# infra_stlink.net
KiCad netlist of a schematic drawn in Altium Designer
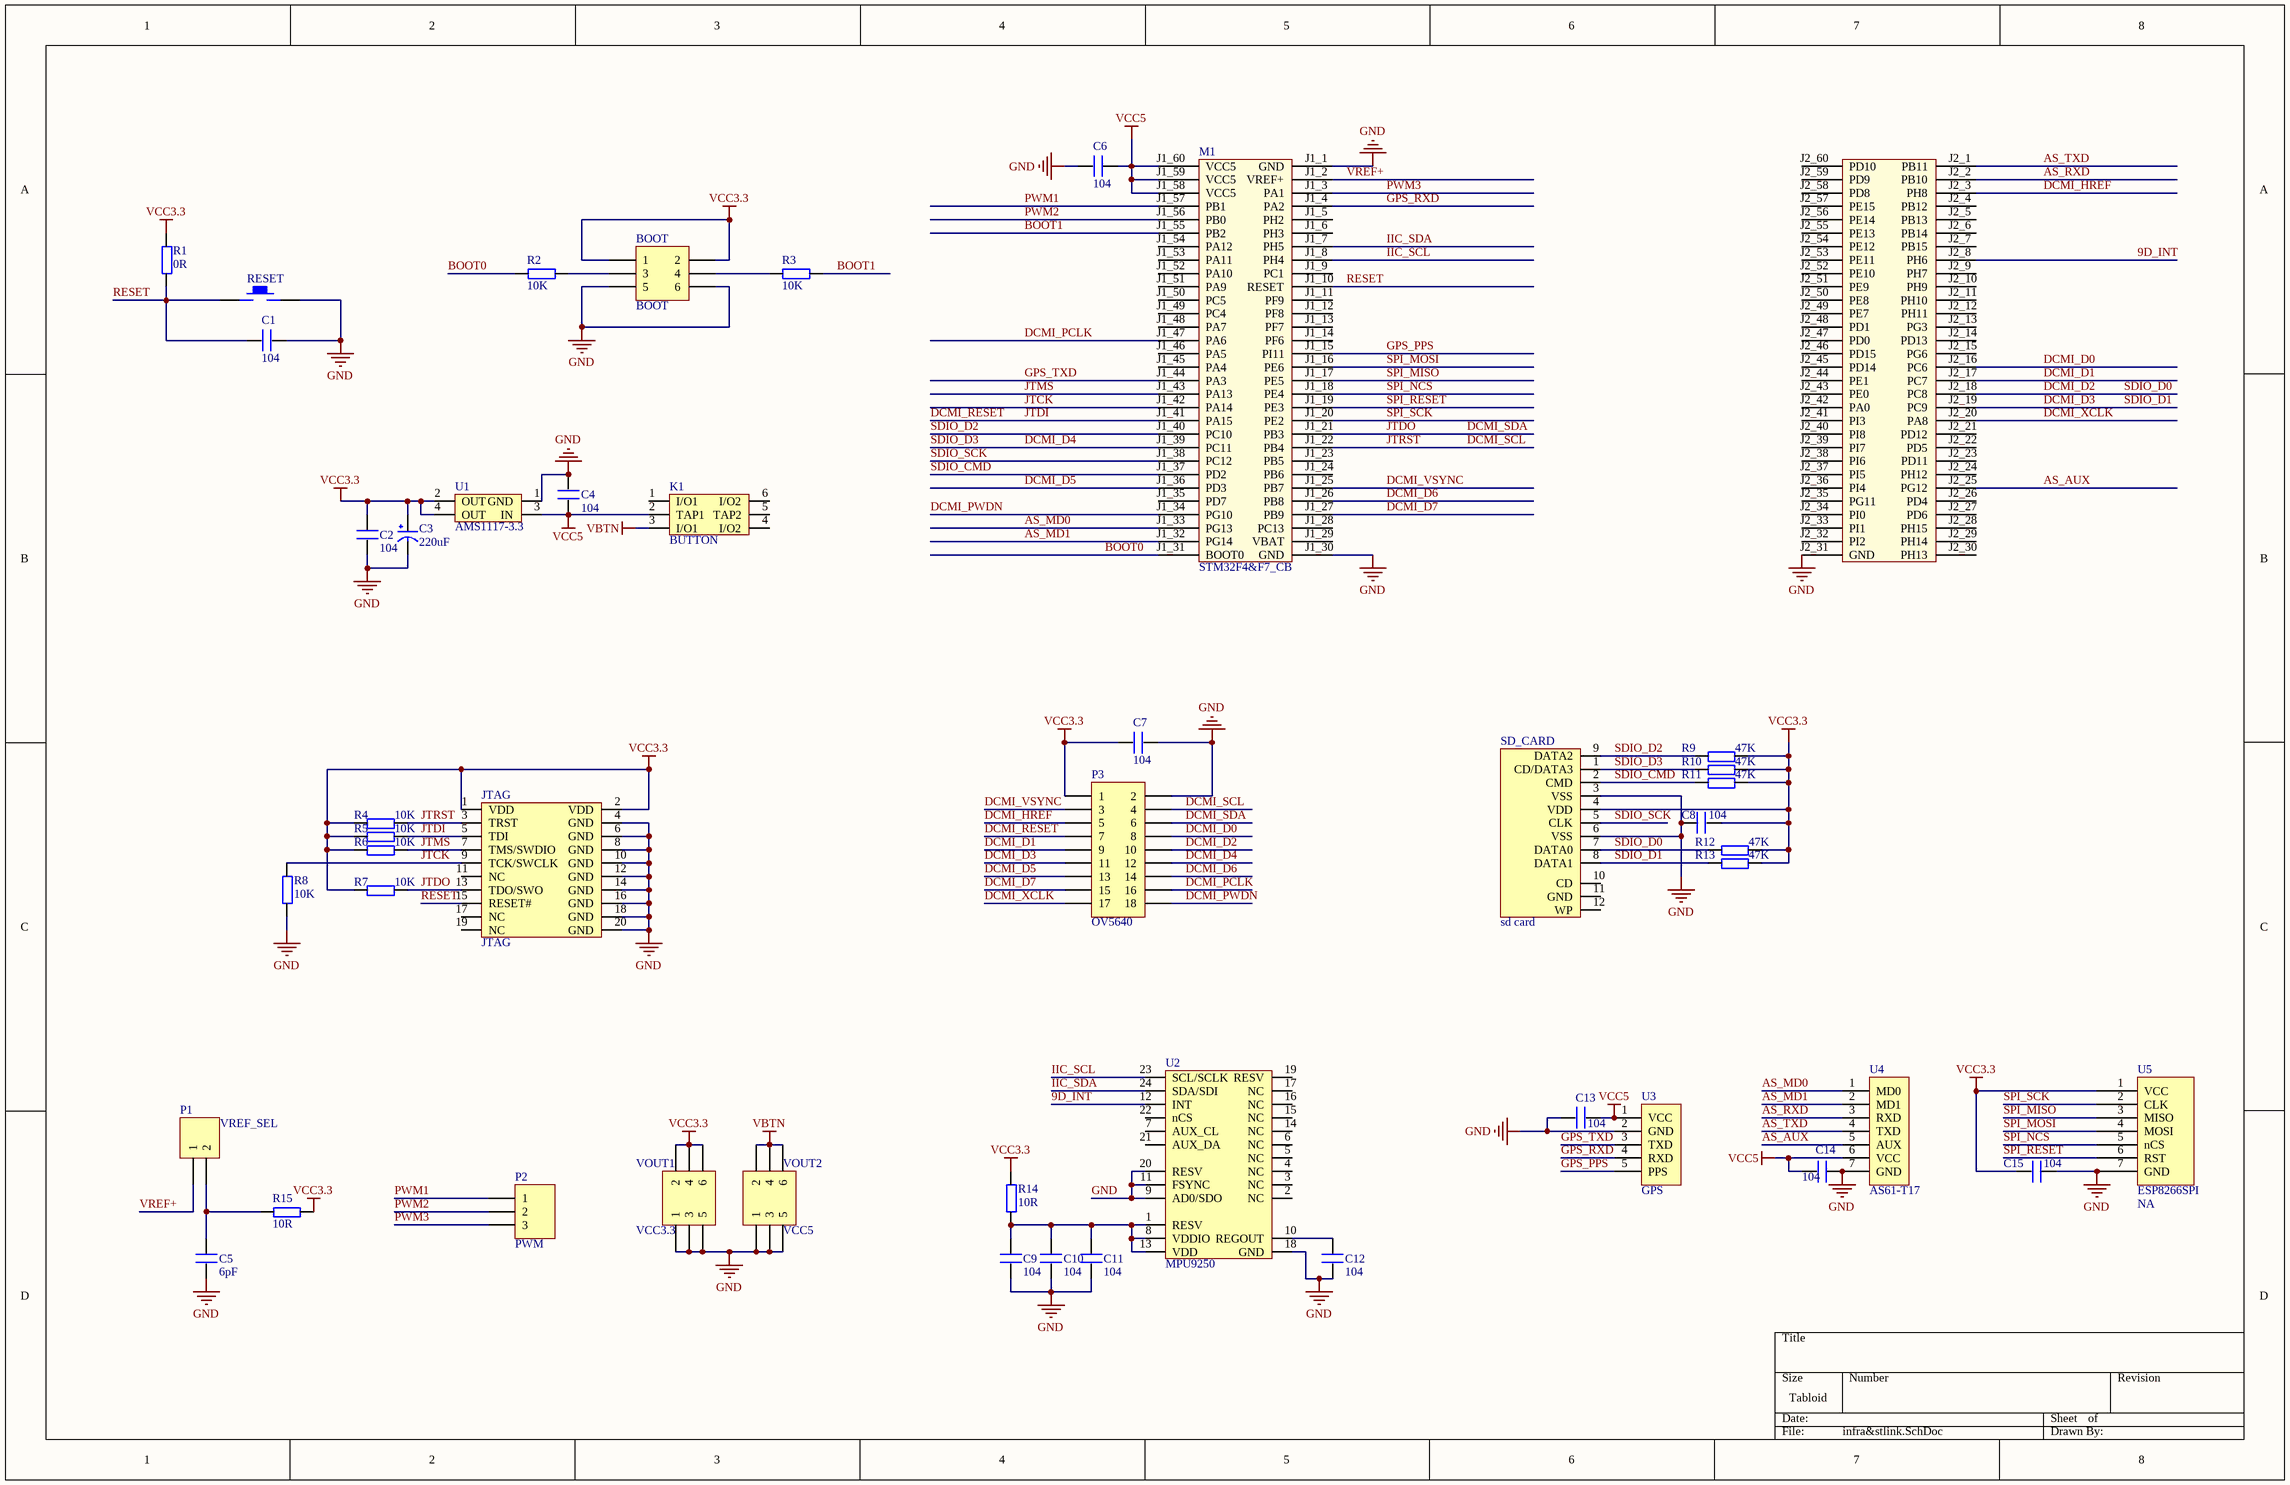
[diagram p0: infra&stlink.SchDoc]

(export (version "E")
  (design (tool "Eeschema 10.0.6"))
  (components
    (comp (ref "BOOT")
      (value "BOOT")
      (footprint "HDR2X3")
      (description "Header, 3-Pin, Dual row")
      (fields (field (name "PUBLISHER") "Altium Limited"))
      (libsource (lib "阿波罗STM32F4&F7底板封装库") (part "Header 3X2"))
    )
    (comp (ref "C1") (value "104") (footprint "0805") (libsource (lib "阿波罗STM32F4&F7底板封装库") (part "C")))
    (comp (ref "C2") (value "104") (footprint "0805") (libsource (lib "阿波罗STM32F4&F7底板封装库") (part "C")))
    (comp (ref "C3")
      (value "220uF")
      (footprint "CC6.56.5")
      (libsource (lib "阿波罗STM32F4&F7底板封装库") (part "CAP"))
    )
    (comp (ref "C4") (value "104") (footprint "0805") (libsource (lib "阿波罗STM32F4&F7底板封装库") (part "C")))
    (comp (ref "C5") (value "6pF") (footprint "0805") (libsource (lib "STM32F767核心板封装库") (part "C")))
    (comp (ref "C6") (value "104") (footprint "0805") (libsource (lib "阿波罗STM32F4&F7底板封装库") (part "C")))
    (comp (ref "C7") (value "104") (footprint "0805") (libsource (lib "STM32F767核心板封装库") (part "C")))
    (comp (ref "C8") (value "104") (footprint "0805") (libsource (lib "阿波罗STM32F4&F7底板封装库") (part "C")))
    (comp (ref "C9") (value "104") (footprint "0805") (libsource (lib "阿波罗STM32F4&F7底板封装库") (part "C")))
    (comp (ref "C10") (value "104") (footprint "0805") (libsource (lib "阿波罗STM32F4&F7底板封装库") (part "C")))
    (comp (ref "C11") (value "104") (footprint "0805") (libsource (lib "阿波罗STM32F4&F7底板封装库") (part "C")))
    (comp (ref "C12") (value "104") (footprint "0805") (libsource (lib "阿波罗STM32F4&F7底板封装库") (part "C")))
    (comp (ref "C13") (value "104") (footprint "0805") (libsource (lib "阿波罗STM32F4&F7底板封装库") (part "C")))
    (comp (ref "C14") (value "104") (footprint "0805") (libsource (lib "阿波罗STM32F4&F7底板封装库") (part "C")))
    (comp (ref "C15") (value "104") (footprint "0805") (libsource (lib "阿波罗STM32F4&F7底板封装库") (part "C")))
    (comp (ref "JTAG")
      (value "JTAG")
      (footprint "JTAG_20")
      (libsource (lib "阿波罗STM32F4&F7底板封装库") (part "JTAG"))
    )
    (comp (ref "K1")
      (value "BUTTON")
      (footprint "BTN8.5*8.5")
      (libsource (lib "阿波罗STM32F4&F7底板封装库") (part "BUTTON"))
    )
    (comp (ref "M1")
      (value "STM32F4&F7_CB")
      (footprint "STM32F4&F7_CB")
      (description "F429/746 Core Board")
      (libsource (lib "阿波罗STM32F4&F7底板封装库") (part "STM32F4&F7_CB"))
    )
    (comp (ref "P1")
      (value "VREF_SEL")
      (footprint "HDR1X2")
      (description "Header, 2-Pin")
      (fields (field (name "PUBLISHER") "Altium Limited"))
      (libsource (lib "阿波罗STM32F4&F7底板封装库") (part "Header 2"))
    )
    (comp (ref "P2")
      (value "PWM")
      (footprint "HDR1X3")
      (description "Header, 3-Pin")
      (fields (field (name "PUBLISHER") "Altium Limited"))
      (libsource (lib "Miscellaneous Connectors") (part "Header 3"))
    )
    (comp (ref "P3")
      (value "OV5640")
      (footprint "HDR2X9")
      (description "Header, 9-Pin, Dual row")
      (fields (field (name "PUBLISHER") "Altium Limited"))
      (libsource (lib "阿波罗STM32F4&F7底板封装库") (part "Header 9X2"))
    )
    (comp (ref "R1") (value "0R") (footprint "0805") (libsource (lib "STM32F767核心板封装库") (part "R")))
    (comp (ref "R2") (value "10K") (footprint "0805") (libsource (lib "STM32F767核心板封装库") (part "R")))
    (comp (ref "R3") (value "10K") (footprint "0805") (libsource (lib "STM32F767核心板封装库") (part "R")))
    (comp (ref "R4") (value "10K") (footprint "0805") (libsource (lib "STM32F767核心板封装库") (part "R")))
    (comp (ref "R5") (value "10K") (footprint "0805") (libsource (lib "STM32F767核心板封装库") (part "R")))
    (comp (ref "R6") (value "10K") (footprint "0805") (libsource (lib "STM32F767核心板封装库") (part "R")))
    (comp (ref "R7") (value "10K") (footprint "0805") (libsource (lib "STM32F767核心板封装库") (part "R")))
    (comp (ref "R8") (value "10K") (footprint "0805") (libsource (lib "STM32F767核心板封装库") (part "R")))
    (comp (ref "R9") (value "47K") (footprint "0805") (libsource (lib "STM32F767核心板封装库") (part "R")))
    (comp (ref "R10") (value "47K") (footprint "0805") (libsource (lib "STM32F767核心板封装库") (part "R")))
    (comp (ref "R11") (value "47K") (footprint "0805") (libsource (lib "STM32F767核心板封装库") (part "R")))
    (comp (ref "R12") (value "47K") (footprint "0805") (libsource (lib "STM32F767核心板封装库") (part "R")))
    (comp (ref "R13") (value "47K") (footprint "0805") (libsource (lib "STM32F767核心板封装库") (part "R")))
    (comp (ref "R14") (value "10R") (footprint "0805") (libsource (lib "STM32F767核心板封装库") (part "R")))
    (comp (ref "R15") (value "10R") (footprint "0805") (libsource (lib "STM32F767核心板封装库") (part "R")))
    (comp (ref "RESET")
      (value "KEY_M")
      (footprint "KEY_M")
      (libsource (lib "阿波罗STM32F4&F7底板封装库") (part "KEY_M"))
    )
    (comp (ref "SD_CARD")
      (value "sd card")
      (footprint "SDCARD_L")
      (libsource (lib "阿波罗STM32F4&F7底板封装库") (part "sd card"))
    )
    (comp (ref "U1")
      (value "AMS1117-3.3")
      (footprint "AMS1117")
      (libsource (lib "阿波罗STM32F4&F7底板封装库") (part "AMS1117"))
    )
    (comp (ref "U2")
      (value "MPU9250")
      (footprint "QFN24-t")
      (description "9轴运动处理传感器")
      (libsource (lib "阿波罗STM32F4&F7底板封装库") (part "MPU9250"))
    )
    (comp (ref "U3")
      (value "GPS")
      (footprint "HDR1X5")
      (description "Header, 5-Pin")
      (fields (field (name "PUBLISHER") "Altium Limited"))
      (libsource (lib "Miscellaneous Connectors") (part "Header 5"))
    )
    (comp (ref "U4")
      (value "AS61-T17")
      (footprint "HDR1X7")
      (description "Header, 7-Pin")
      (fields (field (name "PUBLISHER") "Altium Limited"))
      (libsource (lib "Miscellaneous Connectors") (part "Header 7"))
    )
    (comp (ref "U5")
      (value "NA")
      (footprint "Edge Connector7")
      (libsource (lib "esp8266spi") (part "ESP8266SPI"))
    )
    (comp (ref "VOUT1")
      (value "VCC3.3")
      (footprint "HDR2X3")
      (description "Header, 3-Pin, Dual row")
      (fields (field (name "PUBLISHER") "Altium Limited"))
      (libsource (lib "Miscellaneous Connectors") (part "Header 3X2"))
    )
    (comp (ref "VOUT2")
      (value "VCC5")
      (footprint "HDR2X3")
      (description "Header, 3-Pin, Dual row")
      (fields (field (name "PUBLISHER") "Altium Limited"))
      (libsource (lib "Miscellaneous Connectors") (part "Header 3X2"))
    )
  )
  (nets
    (net (code "1") (name "/9D_INT") (class "Default")
      (node (ref "M1") (pin "J2_8") (pinfunction "PH6_J2_8") (pintype "passive"))
      (node (ref "U2") (pin "12") (pinfunction "INT_12") (pintype "passive"))
    )
    (net (code "2") (name "/AS_AUX") (class "Default")
      (node (ref "M1") (pin "J2_25") (pinfunction "PG12_J2_25") (pintype "passive"))
      (node (ref "U4") (pin "5") (pinfunction "AUX_5") (pintype "passive"))
    )
    (net (code "3") (name "/AS_MD0") (class "Default")
      (node (ref "M1") (pin "J1_33") (pinfunction "PG13_J1_33") (pintype "passive"))
      (node (ref "U4") (pin "1") (pinfunction "MD0_1") (pintype "passive"))
    )
    (net (code "4") (name "/AS_MD1") (class "Default")
      (node (ref "M1") (pin "J1_32") (pinfunction "PG14_J1_32") (pintype "passive"))
      (node (ref "U4") (pin "2") (pinfunction "MD1_2") (pintype "passive"))
    )
    (net (code "5") (name "/AS_RXD") (class "Default")
      (node (ref "M1") (pin "J2_2") (pinfunction "PB10_J2_2") (pintype "passive"))
      (node (ref "U4") (pin "3") (pinfunction "RXD_3") (pintype "passive"))
    )
    (net (code "6") (name "/AS_TXD") (class "Default")
      (node (ref "M1") (pin "J2_1") (pinfunction "PB11_J2_1") (pintype "passive"))
      (node (ref "U4") (pin "4") (pinfunction "TXD_4") (pintype "passive"))
    )
    (net (code "7") (name "/BOOT0") (class "Default")
      (node (ref "M1") (pin "J1_31") (pinfunction "BOOT0_J1_31") (pintype "passive"))
      (node (ref "R2") (pin "1") (pintype "passive"))
    )
    (net (code "8") (name "/BOOT1") (class "Default")
      (node (ref "M1") (pin "J1_55") (pinfunction "PB2_J1_55") (pintype "passive"))
      (node (ref "R3") (pin "2") (pintype "passive"))
    )
    (net (code "9") (name "/DCMI_D0") (class "Default")
      (node (ref "M1") (pin "J2_16") (pinfunction "PC6_J2_16") (pintype "passive"))
      (node (ref "P3") (pin "8") (pinfunction "8_8") (pintype "passive"))
    )
    (net (code "10") (name "/DCMI_D1") (class "Default")
      (node (ref "M1") (pin "J2_17") (pinfunction "PC7_J2_17") (pintype "passive"))
      (node (ref "P3") (pin "9") (pinfunction "9_9") (pintype "passive"))
    )
    (net (code "11") (name "/DCMI_D2") (class "Default")
      (node (ref "M1") (pin "J2_18") (pinfunction "PC8_J2_18") (pintype "passive"))
      (node (ref "P3") (pin "10") (pinfunction "10_10") (pintype "passive"))
      (node (ref "R12") (pin "1") (pintype "passive"))
      (node (ref "SD_CARD") (pin "7") (pinfunction "DATA0_7") (pintype "passive"))
    )
    (net (code "12") (name "/DCMI_D3") (class "Default")
      (node (ref "M1") (pin "J2_19") (pinfunction "PC9_J2_19") (pintype "passive"))
      (node (ref "P3") (pin "11") (pinfunction "11_11") (pintype "passive"))
      (node (ref "R13") (pin "1") (pintype "passive"))
      (node (ref "SD_CARD") (pin "8") (pinfunction "DATA1_8") (pintype "passive"))
    )
    (net (code "13") (name "/DCMI_D4") (class "Default")
      (node (ref "M1") (pin "J1_39") (pinfunction "PC11_J1_39") (pintype "passive"))
      (node (ref "P3") (pin "12") (pinfunction "12_12") (pintype "passive"))
      (node (ref "R10") (pin "1") (pintype "passive"))
      (node (ref "SD_CARD") (pin "1") (pinfunction "CD/DATA3_1") (pintype "passive"))
    )
    (net (code "14") (name "/DCMI_D5") (class "Default")
      (node (ref "M1") (pin "J1_36") (pinfunction "PD3_J1_36") (pintype "passive"))
      (node (ref "P3") (pin "13") (pinfunction "13_13") (pintype "passive"))
    )
    (net (code "15") (name "/DCMI_D6") (class "Default")
      (node (ref "M1") (pin "J1_26") (pinfunction "PB8_J1_26") (pintype "passive"))
      (node (ref "P3") (pin "14") (pinfunction "14_14") (pintype "passive"))
    )
    (net (code "16") (name "/DCMI_D7") (class "Default")
      (node (ref "M1") (pin "J1_27") (pinfunction "PB9_J1_27") (pintype "passive"))
      (node (ref "P3") (pin "15") (pinfunction "15_15") (pintype "passive"))
    )
    (net (code "17") (name "/DCMI_HREF") (class "Default")
      (node (ref "M1") (pin "J2_3") (pinfunction "PH8_J2_3") (pintype "passive"))
      (node (ref "P3") (pin "5") (pinfunction "5_5") (pintype "passive"))
    )
    (net (code "18") (name "/DCMI_PCLK") (class "Default")
      (node (ref "M1") (pin "J1_47") (pinfunction "PA6_J1_47") (pintype "passive"))
      (node (ref "P3") (pin "16") (pinfunction "16_16") (pintype "passive"))
    )
    (net (code "19") (name "/DCMI_PWDN") (class "Default")
      (node (ref "M1") (pin "J1_34") (pinfunction "PG10_J1_34") (pintype "passive"))
      (node (ref "P3") (pin "18") (pinfunction "18_18") (pintype "passive"))
    )
    (net (code "20") (name "/DCMI_RESET") (class "Default")
      (node (ref "JTAG") (pin "5") (pinfunction "TDI_5") (pintype "passive"))
      (node (ref "M1") (pin "J1_41") (pinfunction "PA15_J1_41") (pintype "passive"))
      (node (ref "P3") (pin "7") (pinfunction "7_7") (pintype "passive"))
      (node (ref "R5") (pin "2") (pintype "passive"))
    )
    (net (code "21") (name "/DCMI_SCL") (class "Default")
      (node (ref "JTAG") (pin "3") (pinfunction "TRST_3") (pintype "passive"))
      (node (ref "M1") (pin "J1_22") (pinfunction "PB4_J1_22") (pintype "passive"))
      (node (ref "P3") (pin "4") (pinfunction "4_4") (pintype "passive"))
      (node (ref "R4") (pin "2") (pintype "passive"))
    )
    (net (code "22") (name "/DCMI_SDA") (class "Default")
      (node (ref "JTAG") (pin "13") (pinfunction "TDO/SWO_13") (pintype "passive"))
      (node (ref "M1") (pin "J1_21") (pinfunction "PB3_J1_21") (pintype "passive"))
      (node (ref "P3") (pin "6") (pinfunction "6_6") (pintype "passive"))
      (node (ref "R7") (pin "2") (pintype "passive"))
    )
    (net (code "23") (name "/DCMI_VSYNC") (class "Default")
      (node (ref "M1") (pin "J1_25") (pinfunction "PB7_J1_25") (pintype "passive"))
      (node (ref "P3") (pin "3") (pinfunction "3_3") (pintype "passive"))
    )
    (net (code "24") (name "/DCMI_XCLK") (class "Default")
      (node (ref "M1") (pin "J2_20") (pinfunction "PA8_J2_20") (pintype "passive"))
      (node (ref "P3") (pin "17") (pinfunction "17_17") (pintype "passive"))
    )
    (net (code "25") (name "/GPS_PPS") (class "Default")
      (node (ref "M1") (pin "J1_15") (pinfunction "PI11_J1_15") (pintype "passive"))
      (node (ref "U3") (pin "5") (pinfunction "PPS_5") (pintype "passive"))
    )
    (net (code "26") (name "/GPS_RXD") (class "Default")
      (node (ref "M1") (pin "J1_4") (pinfunction "PA2_J1_4") (pintype "passive"))
      (node (ref "U3") (pin "4") (pinfunction "RXD_4") (pintype "passive"))
    )
    (net (code "27") (name "/GPS_TXD") (class "Default")
      (node (ref "M1") (pin "J1_44") (pinfunction "PA3_J1_44") (pintype "passive"))
      (node (ref "U3") (pin "3") (pinfunction "TXD_3") (pintype "passive"))
    )
    (net (code "28") (name "/IIC_SCL") (class "Default")
      (node (ref "M1") (pin "J1_8") (pinfunction "PH4_J1_8") (pintype "passive"))
      (node (ref "U2") (pin "23") (pinfunction "SCL/SCLK_23") (pintype "passive"))
    )
    (net (code "29") (name "/IIC_SDA") (class "Default")
      (node (ref "M1") (pin "J1_7") (pinfunction "PH5_J1_7") (pintype "passive"))
      (node (ref "U2") (pin "24") (pinfunction "SDA/SDI_24") (pintype "passive"))
    )
    (net (code "30") (name "/JTCK") (class "Default")
      (node (ref "JTAG") (pin "9") (pinfunction "TCK/SWCLK_9") (pintype "passive"))
      (node (ref "M1") (pin "J1_42") (pinfunction "PA14_J1_42") (pintype "passive"))
      (node (ref "R8") (pin "2") (pintype "passive"))
    )
    (net (code "31") (name "/JTMS") (class "Default")
      (node (ref "JTAG") (pin "7") (pinfunction "TMS/SWDIO_7") (pintype "passive"))
      (node (ref "M1") (pin "J1_43") (pinfunction "PA13_J1_43") (pintype "passive"))
      (node (ref "R6") (pin "2") (pintype "passive"))
    )
    (net (code "32") (name "/PWM1") (class "Default")
      (node (ref "M1") (pin "J1_57") (pinfunction "PB1_J1_57") (pintype "passive"))
      (node (ref "P2") (pin "1") (pinfunction "1_1") (pintype "passive"))
    )
    (net (code "33") (name "/PWM2") (class "Default")
      (node (ref "M1") (pin "J1_56") (pinfunction "PB0_J1_56") (pintype "passive"))
      (node (ref "P2") (pin "2") (pinfunction "2_2") (pintype "passive"))
    )
    (net (code "34") (name "/PWM3") (class "Default")
      (node (ref "M1") (pin "J1_3") (pinfunction "PA1_J1_3") (pintype "passive"))
      (node (ref "P2") (pin "3") (pinfunction "3_3") (pintype "passive"))
    )
    (net (code "35") (name "/RESET") (class "Default")
      (node (ref "C1") (pin "1") (pintype "passive"))
      (node (ref "JTAG") (pin "15") (pinfunction "RESET#_15") (pintype "passive"))
      (node (ref "M1") (pin "J1_10") (pinfunction "RESET_J1_10") (pintype "passive"))
      (node (ref "R1") (pin "1") (pintype "passive"))
      (node (ref "RESET") (pin "1") (pinfunction "1_1") (pintype "passive"))
    )
    (net (code "36") (name "/SDIO_CMD") (class "Default")
      (node (ref "M1") (pin "J1_37") (pinfunction "PD2_J1_37") (pintype "passive"))
      (node (ref "R11") (pin "1") (pintype "passive"))
      (node (ref "SD_CARD") (pin "2") (pinfunction "CMD_2") (pintype "passive"))
    )
    (net (code "37") (name "/SDIO_D2") (class "Default")
      (node (ref "M1") (pin "J1_40") (pinfunction "PC10_J1_40") (pintype "passive"))
      (node (ref "R9") (pin "1") (pintype "passive"))
      (node (ref "SD_CARD") (pin "9") (pinfunction "DATA2_9") (pintype "passive"))
    )
    (net (code "38") (name "/SDIO_SCK") (class "Default")
      (node (ref "M1") (pin "J1_38") (pinfunction "PC12_J1_38") (pintype "passive"))
      (node (ref "SD_CARD") (pin "5") (pinfunction "CLK_5") (pintype "passive"))
    )
    (net (code "39") (name "/SPI_MISO") (class "Default")
      (node (ref "M1") (pin "J1_17") (pinfunction "PE5_J1_17") (pintype "passive"))
      (node (ref "U5") (pin "3") (pinfunction "MISO_3") (pintype "passive"))
    )
    (net (code "40") (name "/SPI_MOSI") (class "Default")
      (node (ref "M1") (pin "J1_16") (pinfunction "PE6_J1_16") (pintype "passive"))
      (node (ref "U5") (pin "4") (pinfunction "MOSI_4") (pintype "passive"))
    )
    (net (code "41") (name "/SPI_NCS") (class "Default")
      (node (ref "M1") (pin "J1_18") (pinfunction "PE4_J1_18") (pintype "passive"))
      (node (ref "U5") (pin "5") (pinfunction "nCS_5") (pintype "passive"))
    )
    (net (code "42") (name "/SPI_RESET") (class "Default")
      (node (ref "M1") (pin "J1_19") (pinfunction "PE3_J1_19") (pintype "passive"))
      (node (ref "U5") (pin "6") (pinfunction "RST_6") (pintype "passive"))
    )
    (net (code "43") (name "/SPI_SCK") (class "Default")
      (node (ref "M1") (pin "J1_20") (pinfunction "PE2_J1_20") (pintype "passive"))
      (node (ref "U5") (pin "2") (pinfunction "CLK_2") (pintype "passive"))
    )
    (net (code "44") (name "/VREF+") (class "Default")
      (node (ref "M1") (pin "J1_2") (pinfunction "VREF+_J1_2") (pintype "passive"))
      (node (ref "P1") (pin "1") (pinfunction "1_1") (pintype "passive"))
    )
    (net (code "45") (name "GND") (class "Default")
      (node (ref "BOOT") (pin "5") (pinfunction "5_5") (pintype "passive"))
      (node (ref "BOOT") (pin "6") (pinfunction "6_6") (pintype "passive"))
      (node (ref "C1") (pin "2") (pintype "passive"))
      (node (ref "C10") (pin "1") (pintype "passive"))
      (node (ref "C11") (pin "1") (pintype "passive"))
      (node (ref "C12") (pin "1") (pintype "passive"))
      (node (ref "C13") (pin "1") (pintype "passive"))
      (node (ref "C14") (pin "1") (pintype "passive"))
      (node (ref "C15") (pin "2") (pintype "passive"))
      (node (ref "C2") (pin "1") (pintype "passive"))
      (node (ref "C3") (pin "2") (pinfunction "GND_2") (pintype "passive"))
      (node (ref "C4") (pin "2") (pintype "passive"))
      (node (ref "C5") (pin "1") (pintype "passive"))
      (node (ref "C6") (pin "1") (pintype "passive"))
      (node (ref "C7") (pin "2") (pintype "passive"))
      (node (ref "C8") (pin "1") (pintype "passive"))
      (node (ref "C9") (pin "1") (pintype "passive"))
      (node (ref "JTAG") (pin "10") (pinfunction "GND_10") (pintype "passive"))
      (node (ref "JTAG") (pin "12") (pinfunction "GND_12") (pintype "passive"))
      (node (ref "JTAG") (pin "14") (pinfunction "GND_14") (pintype "passive"))
      (node (ref "JTAG") (pin "16") (pinfunction "GND_16") (pintype "passive"))
      (node (ref "JTAG") (pin "18") (pinfunction "GND_18") (pintype "passive"))
      (node (ref "JTAG") (pin "20") (pinfunction "GND_20") (pintype "passive"))
      (node (ref "JTAG") (pin "4") (pinfunction "GND_4") (pintype "passive"))
      (node (ref "JTAG") (pin "6") (pinfunction "GND_6") (pintype "passive"))
      (node (ref "JTAG") (pin "8") (pinfunction "GND_8") (pintype "passive"))
      (node (ref "M1") (pin "J1_1") (pinfunction "GND_J1_1") (pintype "passive"))
      (node (ref "M1") (pin "J1_30") (pinfunction "GND_J1_30") (pintype "passive"))
      (node (ref "M1") (pin "J2_31") (pinfunction "GND_J2_31") (pintype "passive"))
      (node (ref "P3") (pin "2") (pinfunction "2_2") (pintype "passive"))
      (node (ref "R8") (pin "1") (pintype "passive"))
      (node (ref "RESET") (pin "2") (pinfunction "2_2") (pintype "passive"))
      (node (ref "SD_CARD") (pin "3") (pinfunction "VSS_3") (pintype "passive"))
      (node (ref "SD_CARD") (pin "6") (pinfunction "VSS_6") (pintype "passive"))
      (node (ref "U1") (pin "1") (pinfunction "GND_1") (pintype "passive"))
      (node (ref "U2") (pin "11") (pinfunction "FSYNC_11") (pintype "passive"))
      (node (ref "U2") (pin "18") (pinfunction "GND_18") (pintype "passive"))
      (node (ref "U2") (pin "20") (pinfunction "RESV_20") (pintype "passive"))
      (node (ref "U2") (pin "9") (pinfunction "AD0/SDO_9") (pintype "passive"))
      (node (ref "U3") (pin "2") (pinfunction "GND_2") (pintype "passive"))
      (node (ref "U4") (pin "7") (pinfunction "GND_7") (pintype "passive"))
      (node (ref "U5") (pin "7") (pinfunction "GND_7") (pintype "passive"))
      (node (ref "VOUT1") (pin "1") (pinfunction "1_1") (pintype "passive"))
      (node (ref "VOUT1") (pin "3") (pinfunction "3_3") (pintype "passive"))
      (node (ref "VOUT1") (pin "5") (pinfunction "5_5") (pintype "passive"))
      (node (ref "VOUT2") (pin "1") (pinfunction "1_1") (pintype "passive"))
      (node (ref "VOUT2") (pin "3") (pinfunction "3_3") (pintype "passive"))
      (node (ref "VOUT2") (pin "5") (pinfunction "5_5") (pintype "passive"))
    )
    (net (code "46") (name "Net-(BOOT-Pad3)") (class "Default")
      (node (ref "BOOT") (pin "3") (pinfunction "3_3") (pintype "passive"))
      (node (ref "R2") (pin "2") (pintype "passive"))
    )
    (net (code "47") (name "Net-(BOOT-Pad4)") (class "Default")
      (node (ref "BOOT") (pin "4") (pinfunction "4_4") (pintype "passive"))
      (node (ref "R3") (pin "1") (pintype "passive"))
    )
    (net (code "48") (name "Net-(C5-Pad2)") (class "Default")
      (node (ref "C5") (pin "2") (pintype "passive"))
      (node (ref "P1") (pin "2") (pinfunction "2_2") (pintype "passive"))
      (node (ref "R15") (pin "1") (pintype "passive"))
    )
    (net (code "49") (name "Net-(U2-REGOUT)") (class "Default")
      (node (ref "C12") (pin "2") (pintype "passive"))
      (node (ref "U2") (pin "10") (pinfunction "REGOUT_10") (pintype "passive"))
    )
    (net (code "50") (name "Net-(U2-VDD)") (class "Default")
      (node (ref "C10") (pin "2") (pintype "passive"))
      (node (ref "C11") (pin "2") (pintype "passive"))
      (node (ref "C9") (pin "2") (pintype "passive"))
      (node (ref "R14") (pin "1") (pintype "passive"))
      (node (ref "U2") (pin "1") (pinfunction "RESV_1") (pintype "passive"))
      (node (ref "U2") (pin "13") (pinfunction "VDD_13") (pintype "passive"))
      (node (ref "U2") (pin "8") (pinfunction "VDDIO_8") (pintype "passive"))
    )
    (net (code "51") (name "VBTN") (class "Default")
      (node (ref "K1") (pin "3") (pinfunction "I/O1_3") (pintype "passive"))
      (node (ref "VOUT2") (pin "2") (pinfunction "2_2") (pintype "passive"))
      (node (ref "VOUT2") (pin "4") (pinfunction "4_4") (pintype "passive"))
      (node (ref "VOUT2") (pin "6") (pinfunction "6_6") (pintype "passive"))
    )
    (net (code "52") (name "VCC3.3") (class "Default")
      (node (ref "BOOT") (pin "1") (pinfunction "1_1") (pintype "passive"))
      (node (ref "BOOT") (pin "2") (pinfunction "2_2") (pintype "passive"))
      (node (ref "C15") (pin "1") (pintype "passive"))
      (node (ref "C2") (pin "2") (pintype "passive"))
      (node (ref "C3") (pin "1") (pinfunction "VCC_1") (pintype "passive"))
      (node (ref "C7") (pin "1") (pintype "passive"))
      (node (ref "C8") (pin "2") (pintype "passive"))
      (node (ref "JTAG") (pin "1") (pinfunction "VDD_1") (pintype "passive"))
      (node (ref "JTAG") (pin "2") (pinfunction "VDD_2") (pintype "passive"))
      (node (ref "P3") (pin "1") (pinfunction "1_1") (pintype "passive"))
      (node (ref "R1") (pin "2") (pintype "passive"))
      (node (ref "R10") (pin "2") (pintype "passive"))
      (node (ref "R11") (pin "2") (pintype "passive"))
      (node (ref "R12") (pin "2") (pintype "passive"))
      (node (ref "R13") (pin "2") (pintype "passive"))
      (node (ref "R14") (pin "2") (pintype "passive"))
      (node (ref "R15") (pin "2") (pintype "passive"))
      (node (ref "R4") (pin "1") (pintype "passive"))
      (node (ref "R5") (pin "1") (pintype "passive"))
      (node (ref "R6") (pin "1") (pintype "passive"))
      (node (ref "R7") (pin "1") (pintype "passive"))
      (node (ref "R9") (pin "2") (pintype "passive"))
      (node (ref "SD_CARD") (pin "4") (pinfunction "VDD_4") (pintype "passive"))
      (node (ref "U1") (pin "2") (pinfunction "OUT_2") (pintype "passive"))
      (node (ref "U1") (pin "4") (pinfunction "OUT_4") (pintype "passive"))
      (node (ref "U5") (pin "1") (pinfunction "VCC_1") (pintype "passive"))
      (node (ref "VOUT1") (pin "2") (pinfunction "2_2") (pintype "passive"))
      (node (ref "VOUT1") (pin "4") (pinfunction "4_4") (pintype "passive"))
      (node (ref "VOUT1") (pin "6") (pinfunction "6_6") (pintype "passive"))
    )
    (net (code "53") (name "VCC5") (class "Default")
      (node (ref "C13") (pin "2") (pintype "passive"))
      (node (ref "C14") (pin "2") (pintype "passive"))
      (node (ref "C4") (pin "1") (pintype "passive"))
      (node (ref "C6") (pin "2") (pintype "passive"))
      (node (ref "K1") (pin "2") (pinfunction "TAP1_2") (pintype "passive"))
      (node (ref "M1") (pin "J1_58") (pinfunction "VCC5_J1_58") (pintype "passive"))
      (node (ref "M1") (pin "J1_59") (pinfunction "VCC5_J1_59") (pintype "passive"))
      (node (ref "M1") (pin "J1_60") (pinfunction "VCC5_J1_60") (pintype "passive"))
      (node (ref "U1") (pin "3") (pinfunction "IN_3") (pintype "passive"))
      (node (ref "U3") (pin "1") (pinfunction "VCC_1") (pintype "passive"))
      (node (ref "U4") (pin "6") (pinfunction "VCC_6") (pintype "passive"))
    )
    (net (code "54") (name "unconnected-(JTAG-NC-Pad11)") (class "Default")
      (node (ref "JTAG") (pin "11") (pinfunction "NC_11") (pintype "passive"))
    )
    (net (code "55") (name "unconnected-(JTAG-NC-Pad17)") (class "Default")
      (node (ref "JTAG") (pin "17") (pinfunction "NC_17") (pintype "passive"))
    )
    (net (code "56") (name "unconnected-(JTAG-NC-Pad19)") (class "Default")
      (node (ref "JTAG") (pin "19") (pinfunction "NC_19") (pintype "passive"))
    )
    (net (code "57") (name "unconnected-(K1-I{slash}O1-Pad1)") (class "Default")
      (node (ref "K1") (pin "1") (pinfunction "I/O1_1") (pintype "passive"))
    )
    (net (code "58") (name "unconnected-(K1-I{slash}O2-Pad4)") (class "Default")
      (node (ref "K1") (pin "4") (pinfunction "I/O2_4") (pintype "passive"))
    )
    (net (code "59") (name "unconnected-(K1-I{slash}O2-Pad6)") (class "Default")
      (node (ref "K1") (pin "6") (pinfunction "I/O2_6") (pintype "passive"))
    )
    (net (code "60") (name "unconnected-(K1-TAP2-Pad5)") (class "Default")
      (node (ref "K1") (pin "5") (pinfunction "TAP2_5") (pintype "passive"))
    )
    (net (code "61") (name "unconnected-(M1-PA0-PadJ2_42)") (class "Default")
      (node (ref "M1") (pin "J2_42") (pinfunction "PA0_J2_42") (pintype "passive"))
    )
    (net (code "62") (name "unconnected-(M1-PA4-PadJ1_45)") (class "Default")
      (node (ref "M1") (pin "J1_45") (pinfunction "PA4_J1_45") (pintype "passive"))
    )
    (net (code "63") (name "unconnected-(M1-PA5-PadJ1_46)") (class "Default")
      (node (ref "M1") (pin "J1_46") (pinfunction "PA5_J1_46") (pintype "passive"))
    )
    (net (code "64") (name "unconnected-(M1-PA7-PadJ1_48)") (class "Default")
      (node (ref "M1") (pin "J1_48") (pinfunction "PA7_J1_48") (pintype "passive"))
    )
    (net (code "65") (name "unconnected-(M1-PA9-PadJ1_51)") (class "Default")
      (node (ref "M1") (pin "J1_51") (pinfunction "PA9_J1_51") (pintype "passive"))
    )
    (net (code "66") (name "unconnected-(M1-PA10-PadJ1_52)") (class "Default")
      (node (ref "M1") (pin "J1_52") (pinfunction "PA10_J1_52") (pintype "passive"))
    )
    (net (code "67") (name "unconnected-(M1-PA11-PadJ1_53)") (class "Default")
      (node (ref "M1") (pin "J1_53") (pinfunction "PA11_J1_53") (pintype "passive"))
    )
    (net (code "68") (name "unconnected-(M1-PA12-PadJ1_54)") (class "Default")
      (node (ref "M1") (pin "J1_54") (pinfunction "PA12_J1_54") (pintype "passive"))
    )
    (net (code "69") (name "unconnected-(M1-PB5-PadJ1_23)") (class "Default")
      (node (ref "M1") (pin "J1_23") (pinfunction "PB5_J1_23") (pintype "passive"))
    )
    (net (code "70") (name "unconnected-(M1-PB6-PadJ1_24)") (class "Default")
      (node (ref "M1") (pin "J1_24") (pinfunction "PB6_J1_24") (pintype "passive"))
    )
    (net (code "71") (name "unconnected-(M1-PB12-PadJ2_4)") (class "Default")
      (node (ref "M1") (pin "J2_4") (pinfunction "PB12_J2_4") (pintype "passive"))
    )
    (net (code "72") (name "unconnected-(M1-PB13-PadJ2_5)") (class "Default")
      (node (ref "M1") (pin "J2_5") (pinfunction "PB13_J2_5") (pintype "passive"))
    )
    (net (code "73") (name "unconnected-(M1-PB14-PadJ2_6)") (class "Default")
      (node (ref "M1") (pin "J2_6") (pinfunction "PB14_J2_6") (pintype "passive"))
    )
    (net (code "74") (name "unconnected-(M1-PB15-PadJ2_7)") (class "Default")
      (node (ref "M1") (pin "J2_7") (pinfunction "PB15_J2_7") (pintype "passive"))
    )
    (net (code "75") (name "unconnected-(M1-PC1-PadJ1_9)") (class "Default")
      (node (ref "M1") (pin "J1_9") (pinfunction "PC1_J1_9") (pintype "passive"))
    )
    (net (code "76") (name "unconnected-(M1-PC4-PadJ1_49)") (class "Default")
      (node (ref "M1") (pin "J1_49") (pinfunction "PC4_J1_49") (pintype "passive"))
    )
    (net (code "77") (name "unconnected-(M1-PC5-PadJ1_50)") (class "Default")
      (node (ref "M1") (pin "J1_50") (pinfunction "PC5_J1_50") (pintype "passive"))
    )
    (net (code "78") (name "unconnected-(M1-PC13-PadJ1_28)") (class "Default")
      (node (ref "M1") (pin "J1_28") (pinfunction "PC13_J1_28") (pintype "passive"))
    )
    (net (code "79") (name "unconnected-(M1-PD0-PadJ2_47)") (class "Default")
      (node (ref "M1") (pin "J2_47") (pinfunction "PD0_J2_47") (pintype "passive"))
    )
    (net (code "80") (name "unconnected-(M1-PD1-PadJ2_48)") (class "Default")
      (node (ref "M1") (pin "J2_48") (pinfunction "PD1_J2_48") (pintype "passive"))
    )
    (net (code "81") (name "unconnected-(M1-PD4-PadJ2_26)") (class "Default")
      (node (ref "M1") (pin "J2_26") (pinfunction "PD4_J2_26") (pintype "passive"))
    )
    (net (code "82") (name "unconnected-(M1-PD5-PadJ2_22)") (class "Default")
      (node (ref "M1") (pin "J2_22") (pinfunction "PD5_J2_22") (pintype "passive"))
    )
    (net (code "83") (name "unconnected-(M1-PD6-PadJ2_27)") (class "Default")
      (node (ref "M1") (pin "J2_27") (pinfunction "PD6_J2_27") (pintype "passive"))
    )
    (net (code "84") (name "unconnected-(M1-PD7-PadJ1_35)") (class "Default")
      (node (ref "M1") (pin "J1_35") (pinfunction "PD7_J1_35") (pintype "passive"))
    )
    (net (code "85") (name "unconnected-(M1-PD8-PadJ2_58)") (class "Default")
      (node (ref "M1") (pin "J2_58") (pinfunction "PD8_J2_58") (pintype "passive"))
    )
    (net (code "86") (name "unconnected-(M1-PD9-PadJ2_59)") (class "Default")
      (node (ref "M1") (pin "J2_59") (pinfunction "PD9_J2_59") (pintype "passive"))
    )
    (net (code "87") (name "unconnected-(M1-PD10-PadJ2_60)") (class "Default")
      (node (ref "M1") (pin "J2_60") (pinfunction "PD10_J2_60") (pintype "passive"))
    )
    (net (code "88") (name "unconnected-(M1-PD11-PadJ2_23)") (class "Default")
      (node (ref "M1") (pin "J2_23") (pinfunction "PD11_J2_23") (pintype "passive"))
    )
    (net (code "89") (name "unconnected-(M1-PD12-PadJ2_21)") (class "Default")
      (node (ref "M1") (pin "J2_21") (pinfunction "PD12_J2_21") (pintype "passive"))
    )
    (net (code "90") (name "unconnected-(M1-PD13-PadJ2_14)") (class "Default")
      (node (ref "M1") (pin "J2_14") (pinfunction "PD13_J2_14") (pintype "passive"))
    )
    (net (code "91") (name "unconnected-(M1-PD14-PadJ2_45)") (class "Default")
      (node (ref "M1") (pin "J2_45") (pinfunction "PD14_J2_45") (pintype "passive"))
    )
    (net (code "92") (name "unconnected-(M1-PD15-PadJ2_46)") (class "Default")
      (node (ref "M1") (pin "J2_46") (pinfunction "PD15_J2_46") (pintype "passive"))
    )
    (net (code "93") (name "unconnected-(M1-PE0-PadJ2_43)") (class "Default")
      (node (ref "M1") (pin "J2_43") (pinfunction "PE0_J2_43") (pintype "passive"))
    )
    (net (code "94") (name "unconnected-(M1-PE1-PadJ2_44)") (class "Default")
      (node (ref "M1") (pin "J2_44") (pinfunction "PE1_J2_44") (pintype "passive"))
    )
    (net (code "95") (name "unconnected-(M1-PE7-PadJ2_49)") (class "Default")
      (node (ref "M1") (pin "J2_49") (pinfunction "PE7_J2_49") (pintype "passive"))
    )
    (net (code "96") (name "unconnected-(M1-PE8-PadJ2_50)") (class "Default")
      (node (ref "M1") (pin "J2_50") (pinfunction "PE8_J2_50") (pintype "passive"))
    )
    (net (code "97") (name "unconnected-(M1-PE9-PadJ2_51)") (class "Default")
      (node (ref "M1") (pin "J2_51") (pinfunction "PE9_J2_51") (pintype "passive"))
    )
    (net (code "98") (name "unconnected-(M1-PE10-PadJ2_52)") (class "Default")
      (node (ref "M1") (pin "J2_52") (pinfunction "PE10_J2_52") (pintype "passive"))
    )
    (net (code "99") (name "unconnected-(M1-PE11-PadJ2_53)") (class "Default")
      (node (ref "M1") (pin "J2_53") (pinfunction "PE11_J2_53") (pintype "passive"))
    )
    (net (code "100") (name "unconnected-(M1-PE12-PadJ2_54)") (class "Default")
      (node (ref "M1") (pin "J2_54") (pinfunction "PE12_J2_54") (pintype "passive"))
    )
    (net (code "101") (name "unconnected-(M1-PE13-PadJ2_55)") (class "Default")
      (node (ref "M1") (pin "J2_55") (pinfunction "PE13_J2_55") (pintype "passive"))
    )
    (net (code "102") (name "unconnected-(M1-PE14-PadJ2_56)") (class "Default")
      (node (ref "M1") (pin "J2_56") (pinfunction "PE14_J2_56") (pintype "passive"))
    )
    (net (code "103") (name "unconnected-(M1-PE15-PadJ2_57)") (class "Default")
      (node (ref "M1") (pin "J2_57") (pinfunction "PE15_J2_57") (pintype "passive"))
    )
    (net (code "104") (name "unconnected-(M1-PF6-PadJ1_14)") (class "Default")
      (node (ref "M1") (pin "J1_14") (pinfunction "PF6_J1_14") (pintype "passive"))
    )
    (net (code "105") (name "unconnected-(M1-PF7-PadJ1_13)") (class "Default")
      (node (ref "M1") (pin "J1_13") (pinfunction "PF7_J1_13") (pintype "passive"))
    )
    (net (code "106") (name "unconnected-(M1-PF8-PadJ1_12)") (class "Default")
      (node (ref "M1") (pin "J1_12") (pinfunction "PF8_J1_12") (pintype "passive"))
    )
    (net (code "107") (name "unconnected-(M1-PF9-PadJ1_11)") (class "Default")
      (node (ref "M1") (pin "J1_11") (pinfunction "PF9_J1_11") (pintype "passive"))
    )
    (net (code "108") (name "unconnected-(M1-PG3-PadJ2_13)") (class "Default")
      (node (ref "M1") (pin "J2_13") (pinfunction "PG3_J2_13") (pintype "passive"))
    )
    (net (code "109") (name "unconnected-(M1-PG6-PadJ2_15)") (class "Default")
      (node (ref "M1") (pin "J2_15") (pinfunction "PG6_J2_15") (pintype "passive"))
    )
    (net (code "110") (name "unconnected-(M1-PG11-PadJ2_35)") (class "Default")
      (node (ref "M1") (pin "J2_35") (pinfunction "PG11_J2_35") (pintype "passive"))
    )
    (net (code "111") (name "unconnected-(M1-PH2-PadJ1_5)") (class "Default")
      (node (ref "M1") (pin "J1_5") (pinfunction "PH2_J1_5") (pintype "passive"))
    )
    (net (code "112") (name "unconnected-(M1-PH3-PadJ1_6)") (class "Default")
      (node (ref "M1") (pin "J1_6") (pinfunction "PH3_J1_6") (pintype "passive"))
    )
    (net (code "113") (name "unconnected-(M1-PH7-PadJ2_9)") (class "Default")
      (node (ref "M1") (pin "J2_9") (pinfunction "PH7_J2_9") (pintype "passive"))
    )
    (net (code "114") (name "unconnected-(M1-PH9-PadJ2_10)") (class "Default")
      (node (ref "M1") (pin "J2_10") (pinfunction "PH9_J2_10") (pintype "passive"))
    )
    (net (code "115") (name "unconnected-(M1-PH10-PadJ2_11)") (class "Default")
      (node (ref "M1") (pin "J2_11") (pinfunction "PH10_J2_11") (pintype "passive"))
    )
    (net (code "116") (name "unconnected-(M1-PH11-PadJ2_12)") (class "Default")
      (node (ref "M1") (pin "J2_12") (pinfunction "PH11_J2_12") (pintype "passive"))
    )
    (net (code "117") (name "unconnected-(M1-PH12-PadJ2_24)") (class "Default")
      (node (ref "M1") (pin "J2_24") (pinfunction "PH12_J2_24") (pintype "passive"))
    )
    (net (code "118") (name "unconnected-(M1-PH13-PadJ2_30)") (class "Default")
      (node (ref "M1") (pin "J2_30") (pinfunction "PH13_J2_30") (pintype "passive"))
    )
    (net (code "119") (name "unconnected-(M1-PH14-PadJ2_29)") (class "Default")
      (node (ref "M1") (pin "J2_29") (pinfunction "PH14_J2_29") (pintype "passive"))
    )
    (net (code "120") (name "unconnected-(M1-PH15-PadJ2_28)") (class "Default")
      (node (ref "M1") (pin "J2_28") (pinfunction "PH15_J2_28") (pintype "passive"))
    )
    (net (code "121") (name "unconnected-(M1-PI0-PadJ2_34)") (class "Default")
      (node (ref "M1") (pin "J2_34") (pinfunction "PI0_J2_34") (pintype "passive"))
    )
    (net (code "122") (name "unconnected-(M1-PI1-PadJ2_33)") (class "Default")
      (node (ref "M1") (pin "J2_33") (pinfunction "PI1_J2_33") (pintype "passive"))
    )
    (net (code "123") (name "unconnected-(M1-PI2-PadJ2_32)") (class "Default")
      (node (ref "M1") (pin "J2_32") (pinfunction "PI2_J2_32") (pintype "passive"))
    )
    (net (code "124") (name "unconnected-(M1-PI3-PadJ2_41)") (class "Default")
      (node (ref "M1") (pin "J2_41") (pinfunction "PI3_J2_41") (pintype "passive"))
    )
    (net (code "125") (name "unconnected-(M1-PI4-PadJ2_36)") (class "Default")
      (node (ref "M1") (pin "J2_36") (pinfunction "PI4_J2_36") (pintype "passive"))
    )
    (net (code "126") (name "unconnected-(M1-PI5-PadJ2_37)") (class "Default")
      (node (ref "M1") (pin "J2_37") (pinfunction "PI5_J2_37") (pintype "passive"))
    )
    (net (code "127") (name "unconnected-(M1-PI6-PadJ2_38)") (class "Default")
      (node (ref "M1") (pin "J2_38") (pinfunction "PI6_J2_38") (pintype "passive"))
    )
    (net (code "128") (name "unconnected-(M1-PI7-PadJ2_39)") (class "Default")
      (node (ref "M1") (pin "J2_39") (pinfunction "PI7_J2_39") (pintype "passive"))
    )
    (net (code "129") (name "unconnected-(M1-PI8-PadJ2_40)") (class "Default")
      (node (ref "M1") (pin "J2_40") (pinfunction "PI8_J2_40") (pintype "passive"))
    )
    (net (code "130") (name "unconnected-(M1-VBAT-PadJ1_29)") (class "Default")
      (node (ref "M1") (pin "J1_29") (pinfunction "VBAT_J1_29") (pintype "passive"))
    )
    (net (code "131") (name "unconnected-(SD_CARD-CD-Pad10)") (class "Default")
      (node (ref "SD_CARD") (pin "10") (pinfunction "CD_10") (pintype "passive"))
    )
    (net (code "132") (name "unconnected-(SD_CARD-GND-Pad11)") (class "Default")
      (node (ref "SD_CARD") (pin "11") (pinfunction "GND_11") (pintype "passive"))
    )
    (net (code "133") (name "unconnected-(SD_CARD-WP-Pad12)") (class "Default")
      (node (ref "SD_CARD") (pin "12") (pinfunction "WP_12") (pintype "passive"))
    )
    (net (code "134") (name "unconnected-(U2-AUX_CL-Pad7)") (class "Default")
      (node (ref "U2") (pin "7") (pinfunction "AUX_CL_7") (pintype "passive"))
    )
    (net (code "135") (name "unconnected-(U2-AUX_DA-Pad21)") (class "Default")
      (node (ref "U2") (pin "21") (pinfunction "AUX_DA_21") (pintype "passive"))
    )
    (net (code "136") (name "unconnected-(U2-NC-Pad2)") (class "Default")
      (node (ref "U2") (pin "2") (pinfunction "NC_2") (pintype "passive"))
    )
    (net (code "137") (name "unconnected-(U2-NC-Pad3)") (class "Default")
      (node (ref "U2") (pin "3") (pinfunction "NC_3") (pintype "passive"))
    )
    (net (code "138") (name "unconnected-(U2-NC-Pad4)") (class "Default")
      (node (ref "U2") (pin "4") (pinfunction "NC_4") (pintype "passive"))
    )
    (net (code "139") (name "unconnected-(U2-NC-Pad5)") (class "Default")
      (node (ref "U2") (pin "5") (pinfunction "NC_5") (pintype "passive"))
    )
    (net (code "140") (name "unconnected-(U2-NC-Pad6)") (class "Default")
      (node (ref "U2") (pin "6") (pinfunction "NC_6") (pintype "passive"))
    )
    (net (code "141") (name "unconnected-(U2-NC-Pad14)") (class "Default")
      (node (ref "U2") (pin "14") (pinfunction "NC_14") (pintype "passive"))
    )
    (net (code "142") (name "unconnected-(U2-NC-Pad15)") (class "Default")
      (node (ref "U2") (pin "15") (pinfunction "NC_15") (pintype "passive"))
    )
    (net (code "143") (name "unconnected-(U2-NC-Pad16)") (class "Default")
      (node (ref "U2") (pin "16") (pinfunction "NC_16") (pintype "passive"))
    )
    (net (code "144") (name "unconnected-(U2-NC-Pad17)") (class "Default")
      (node (ref "U2") (pin "17") (pinfunction "NC_17") (pintype "passive"))
    )
    (net (code "145") (name "unconnected-(U2-RESV-Pad19)") (class "Default")
      (node (ref "U2") (pin "19") (pinfunction "RESV_19") (pintype "passive"))
    )
    (net (code "146") (name "unconnected-(U2-nCS-Pad22)") (class "Default")
      (node (ref "U2") (pin "22") (pinfunction "nCS_22") (pintype "passive"))
    )
  )
)
